# Switch_RGB_Cherry.net
KiCad netlist of a schematic drawn in Altium Designer
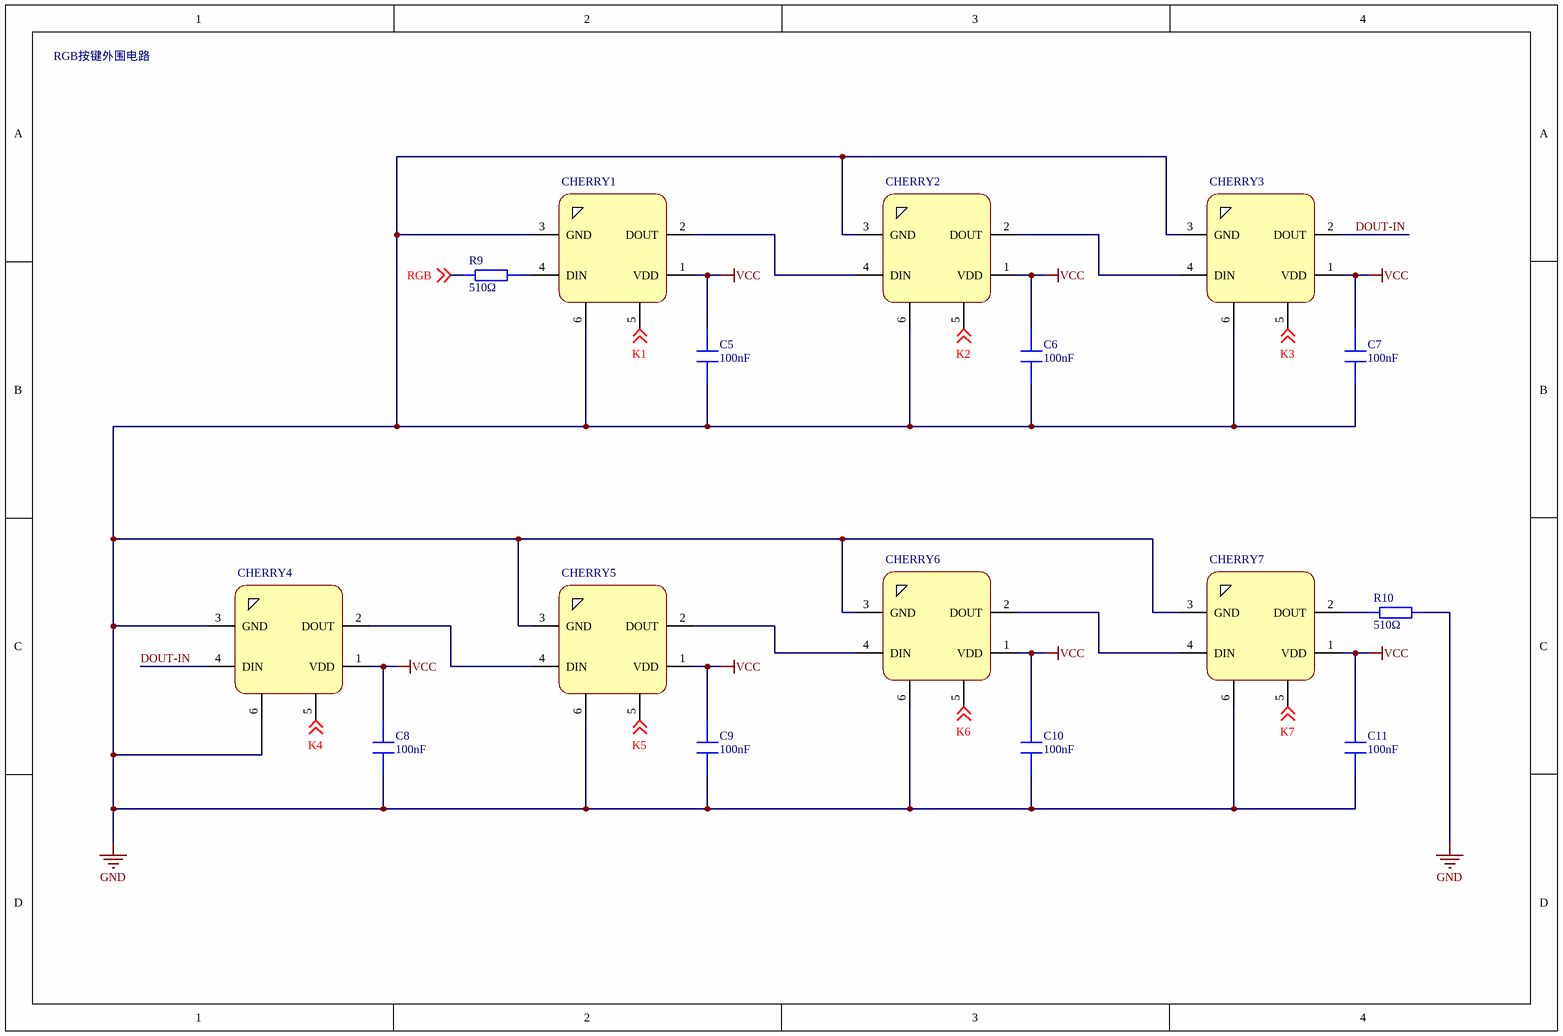
[diagram p0: Switch_RGB_Cherry.SchDoc]

(export (version "E")
  (design (tool "Eeschema 10.0.6"))
  (components
    (comp (ref "C5")
      (value "100nF")
      (footprint "SM_C_0805")
      (description "贴片电容")
      (libsource (lib "Lib_Personal_ByZ") (part "C0805"))
    )
    (comp (ref "C6")
      (value "100nF")
      (footprint "SM_C_0805")
      (description "贴片电容")
      (libsource (lib "Lib_Personal_ByZ") (part "C0805"))
    )
    (comp (ref "C7")
      (value "100nF")
      (footprint "SM_C_0805")
      (description "贴片电容")
      (libsource (lib "Lib_Personal_ByZ") (part "C0805"))
    )
    (comp (ref "C8")
      (value "100nF")
      (footprint "SM_C_0805")
      (description "贴片电容")
      (libsource (lib "Lib_Personal_ByZ") (part "C0805"))
    )
    (comp (ref "C9")
      (value "100nF")
      (footprint "SM_C_0805")
      (description "贴片电容")
      (libsource (lib "Lib_Personal_ByZ") (part "C0805"))
    )
    (comp (ref "C10")
      (value "100nF")
      (footprint "SM_C_0805")
      (description "贴片电容")
      (libsource (lib "Lib_Personal_ByZ") (part "C0805"))
    )
    (comp (ref "C11")
      (value "100nF")
      (footprint "SM_C_0805")
      (description "贴片电容")
      (libsource (lib "Lib_Personal_ByZ") (part "C0805"))
    )
    (comp (ref "CHERRY1")
      (value "Cherry_RGB")
      (footprint "Cherry")
      (description "樱花轴CHERRY")
      (libsource (lib "Lib_Personal_ByZ") (part "Cherry_RGB"))
    )
    (comp (ref "CHERRY2")
      (value "Cherry_RGB")
      (footprint "Cherry")
      (description "樱花轴CHERRY")
      (libsource (lib "Lib_Personal_ByZ") (part "Cherry_RGB"))
    )
    (comp (ref "CHERRY3")
      (value "Cherry_RGB")
      (footprint "Cherry")
      (description "樱花轴CHERRY")
      (libsource (lib "Lib_Personal_ByZ") (part "Cherry_RGB"))
    )
    (comp (ref "CHERRY4")
      (value "Cherry_RGB")
      (footprint "Cherry")
      (description "樱花轴CHERRY")
      (libsource (lib "Lib_Personal_ByZ") (part "Cherry_RGB"))
    )
    (comp (ref "CHERRY5")
      (value "Cherry_RGB")
      (footprint "Cherry")
      (description "樱花轴CHERRY")
      (libsource (lib "Lib_Personal_ByZ") (part "Cherry_RGB"))
    )
    (comp (ref "CHERRY6")
      (value "Cherry_RGB")
      (footprint "Cherry")
      (description "樱花轴CHERRY")
      (libsource (lib "Lib_Personal_ByZ") (part "Cherry_RGB"))
    )
    (comp (ref "CHERRY7")
      (value "Cherry_RGB")
      (footprint "Cherry")
      (description "樱花轴CHERRY")
      (libsource (lib "Lib_Personal_ByZ") (part "Cherry_RGB"))
    )
    (comp (ref "R9")
      (value "510Ω")
      (footprint "SM_R_0805")
      (description "贴片电阻")
      (libsource (lib "Lib_Personal_ByZ") (part "R0805"))
    )
    (comp (ref "R10")
      (value "510Ω")
      (footprint "SM_R_0805")
      (description "贴片电阻")
      (libsource (lib "Lib_Personal_ByZ") (part "R0805"))
    )
  )
  (nets
    (net (code "1") (name "/DOUT-IN") (class "Default")
      (node (ref "CHERRY3") (pin "2") (pinfunction "DOUT_2") (pintype "passive"))
      (node (ref "CHERRY4") (pin "4") (pinfunction "DIN_4") (pintype "passive"))
    )
    (net (code "2") (name "GND") (class "Default")
      (node (ref "C10") (pin "1") (pinfunction "1_1") (pintype "passive"))
      (node (ref "C11") (pin "1") (pinfunction "1_1") (pintype "passive"))
      (node (ref "C5") (pin "1") (pinfunction "1_1") (pintype "passive"))
      (node (ref "C6") (pin "1") (pinfunction "1_1") (pintype "passive"))
      (node (ref "C7") (pin "1") (pinfunction "1_1") (pintype "passive"))
      (node (ref "C8") (pin "1") (pinfunction "1_1") (pintype "passive"))
      (node (ref "C9") (pin "1") (pinfunction "1_1") (pintype "passive"))
      (node (ref "CHERRY1") (pin "3") (pinfunction "GND_3") (pintype "passive"))
      (node (ref "CHERRY1") (pin "6") (pinfunction "KI_6") (pintype "passive"))
      (node (ref "CHERRY2") (pin "3") (pinfunction "GND_3") (pintype "passive"))
      (node (ref "CHERRY2") (pin "6") (pinfunction "KI_6") (pintype "passive"))
      (node (ref "CHERRY3") (pin "3") (pinfunction "GND_3") (pintype "passive"))
      (node (ref "CHERRY3") (pin "6") (pinfunction "KI_6") (pintype "passive"))
      (node (ref "CHERRY4") (pin "3") (pinfunction "GND_3") (pintype "passive"))
      (node (ref "CHERRY4") (pin "6") (pinfunction "KI_6") (pintype "passive"))
      (node (ref "CHERRY5") (pin "3") (pinfunction "GND_3") (pintype "passive"))
      (node (ref "CHERRY5") (pin "6") (pinfunction "KI_6") (pintype "passive"))
      (node (ref "CHERRY6") (pin "3") (pinfunction "GND_3") (pintype "passive"))
      (node (ref "CHERRY6") (pin "6") (pinfunction "KI_6") (pintype "passive"))
      (node (ref "CHERRY7") (pin "3") (pinfunction "GND_3") (pintype "passive"))
      (node (ref "CHERRY7") (pin "6") (pinfunction "KI_6") (pintype "passive"))
      (node (ref "R10") (pin "2") (pinfunction "2_2") (pintype "passive"))
    )
    (net (code "3") (name "K1") (class "Default")
      (node (ref "CHERRY1") (pin "5") (pinfunction "KO_5") (pintype "passive"))
    )
    (net (code "4") (name "K2") (class "Default")
      (node (ref "CHERRY2") (pin "5") (pinfunction "KO_5") (pintype "passive"))
    )
    (net (code "5") (name "K3") (class "Default")
      (node (ref "CHERRY3") (pin "5") (pinfunction "KO_5") (pintype "passive"))
    )
    (net (code "6") (name "K4") (class "Default")
      (node (ref "CHERRY4") (pin "5") (pinfunction "KO_5") (pintype "passive"))
    )
    (net (code "7") (name "K5") (class "Default")
      (node (ref "CHERRY5") (pin "5") (pinfunction "KO_5") (pintype "passive"))
    )
    (net (code "8") (name "K6") (class "Default")
      (node (ref "CHERRY6") (pin "5") (pinfunction "KO_5") (pintype "passive"))
    )
    (net (code "9") (name "K7") (class "Default")
      (node (ref "CHERRY7") (pin "5") (pinfunction "KO_5") (pintype "passive"))
    )
    (net (code "10") (name "Net-(CHERRY1-DIN)") (class "Default")
      (node (ref "CHERRY1") (pin "4") (pinfunction "DIN_4") (pintype "passive"))
      (node (ref "R9") (pin "2") (pinfunction "2_2") (pintype "passive"))
    )
    (net (code "11") (name "Net-(CHERRY1-DOUT)") (class "Default")
      (node (ref "CHERRY1") (pin "2") (pinfunction "DOUT_2") (pintype "passive"))
      (node (ref "CHERRY2") (pin "4") (pinfunction "DIN_4") (pintype "passive"))
    )
    (net (code "12") (name "Net-(CHERRY2-DOUT)") (class "Default")
      (node (ref "CHERRY2") (pin "2") (pinfunction "DOUT_2") (pintype "passive"))
      (node (ref "CHERRY3") (pin "4") (pinfunction "DIN_4") (pintype "passive"))
    )
    (net (code "13") (name "Net-(CHERRY4-DOUT)") (class "Default")
      (node (ref "CHERRY4") (pin "2") (pinfunction "DOUT_2") (pintype "passive"))
      (node (ref "CHERRY5") (pin "4") (pinfunction "DIN_4") (pintype "passive"))
    )
    (net (code "14") (name "Net-(CHERRY5-DOUT)") (class "Default")
      (node (ref "CHERRY5") (pin "2") (pinfunction "DOUT_2") (pintype "passive"))
      (node (ref "CHERRY6") (pin "4") (pinfunction "DIN_4") (pintype "passive"))
    )
    (net (code "15") (name "Net-(CHERRY6-DOUT)") (class "Default")
      (node (ref "CHERRY6") (pin "2") (pinfunction "DOUT_2") (pintype "passive"))
      (node (ref "CHERRY7") (pin "4") (pinfunction "DIN_4") (pintype "passive"))
    )
    (net (code "16") (name "Net-(CHERRY7-DOUT)") (class "Default")
      (node (ref "CHERRY7") (pin "2") (pinfunction "DOUT_2") (pintype "passive"))
      (node (ref "R10") (pin "1") (pinfunction "1_1") (pintype "passive"))
    )
    (net (code "17") (name "RGB") (class "Default")
      (node (ref "R9") (pin "1") (pinfunction "1_1") (pintype "passive"))
    )
    (net (code "18") (name "VCC") (class "Default")
      (node (ref "C10") (pin "2") (pinfunction "2_2") (pintype "passive"))
      (node (ref "C11") (pin "2") (pinfunction "2_2") (pintype "passive"))
      (node (ref "C5") (pin "2") (pinfunction "2_2") (pintype "passive"))
      (node (ref "C6") (pin "2") (pinfunction "2_2") (pintype "passive"))
      (node (ref "C7") (pin "2") (pinfunction "2_2") (pintype "passive"))
      (node (ref "C8") (pin "2") (pinfunction "2_2") (pintype "passive"))
      (node (ref "C9") (pin "2") (pinfunction "2_2") (pintype "passive"))
      (node (ref "CHERRY1") (pin "1") (pinfunction "VDD_1") (pintype "passive"))
      (node (ref "CHERRY2") (pin "1") (pinfunction "VDD_1") (pintype "passive"))
      (node (ref "CHERRY3") (pin "1") (pinfunction "VDD_1") (pintype "passive"))
      (node (ref "CHERRY4") (pin "1") (pinfunction "VDD_1") (pintype "passive"))
      (node (ref "CHERRY5") (pin "1") (pinfunction "VDD_1") (pintype "passive"))
      (node (ref "CHERRY6") (pin "1") (pinfunction "VDD_1") (pintype "passive"))
      (node (ref "CHERRY7") (pin "1") (pinfunction "VDD_1") (pintype "passive"))
    )
  )
)
